# Bt_Drone.net
KiCad netlist of a schematic drawn in EAGLE
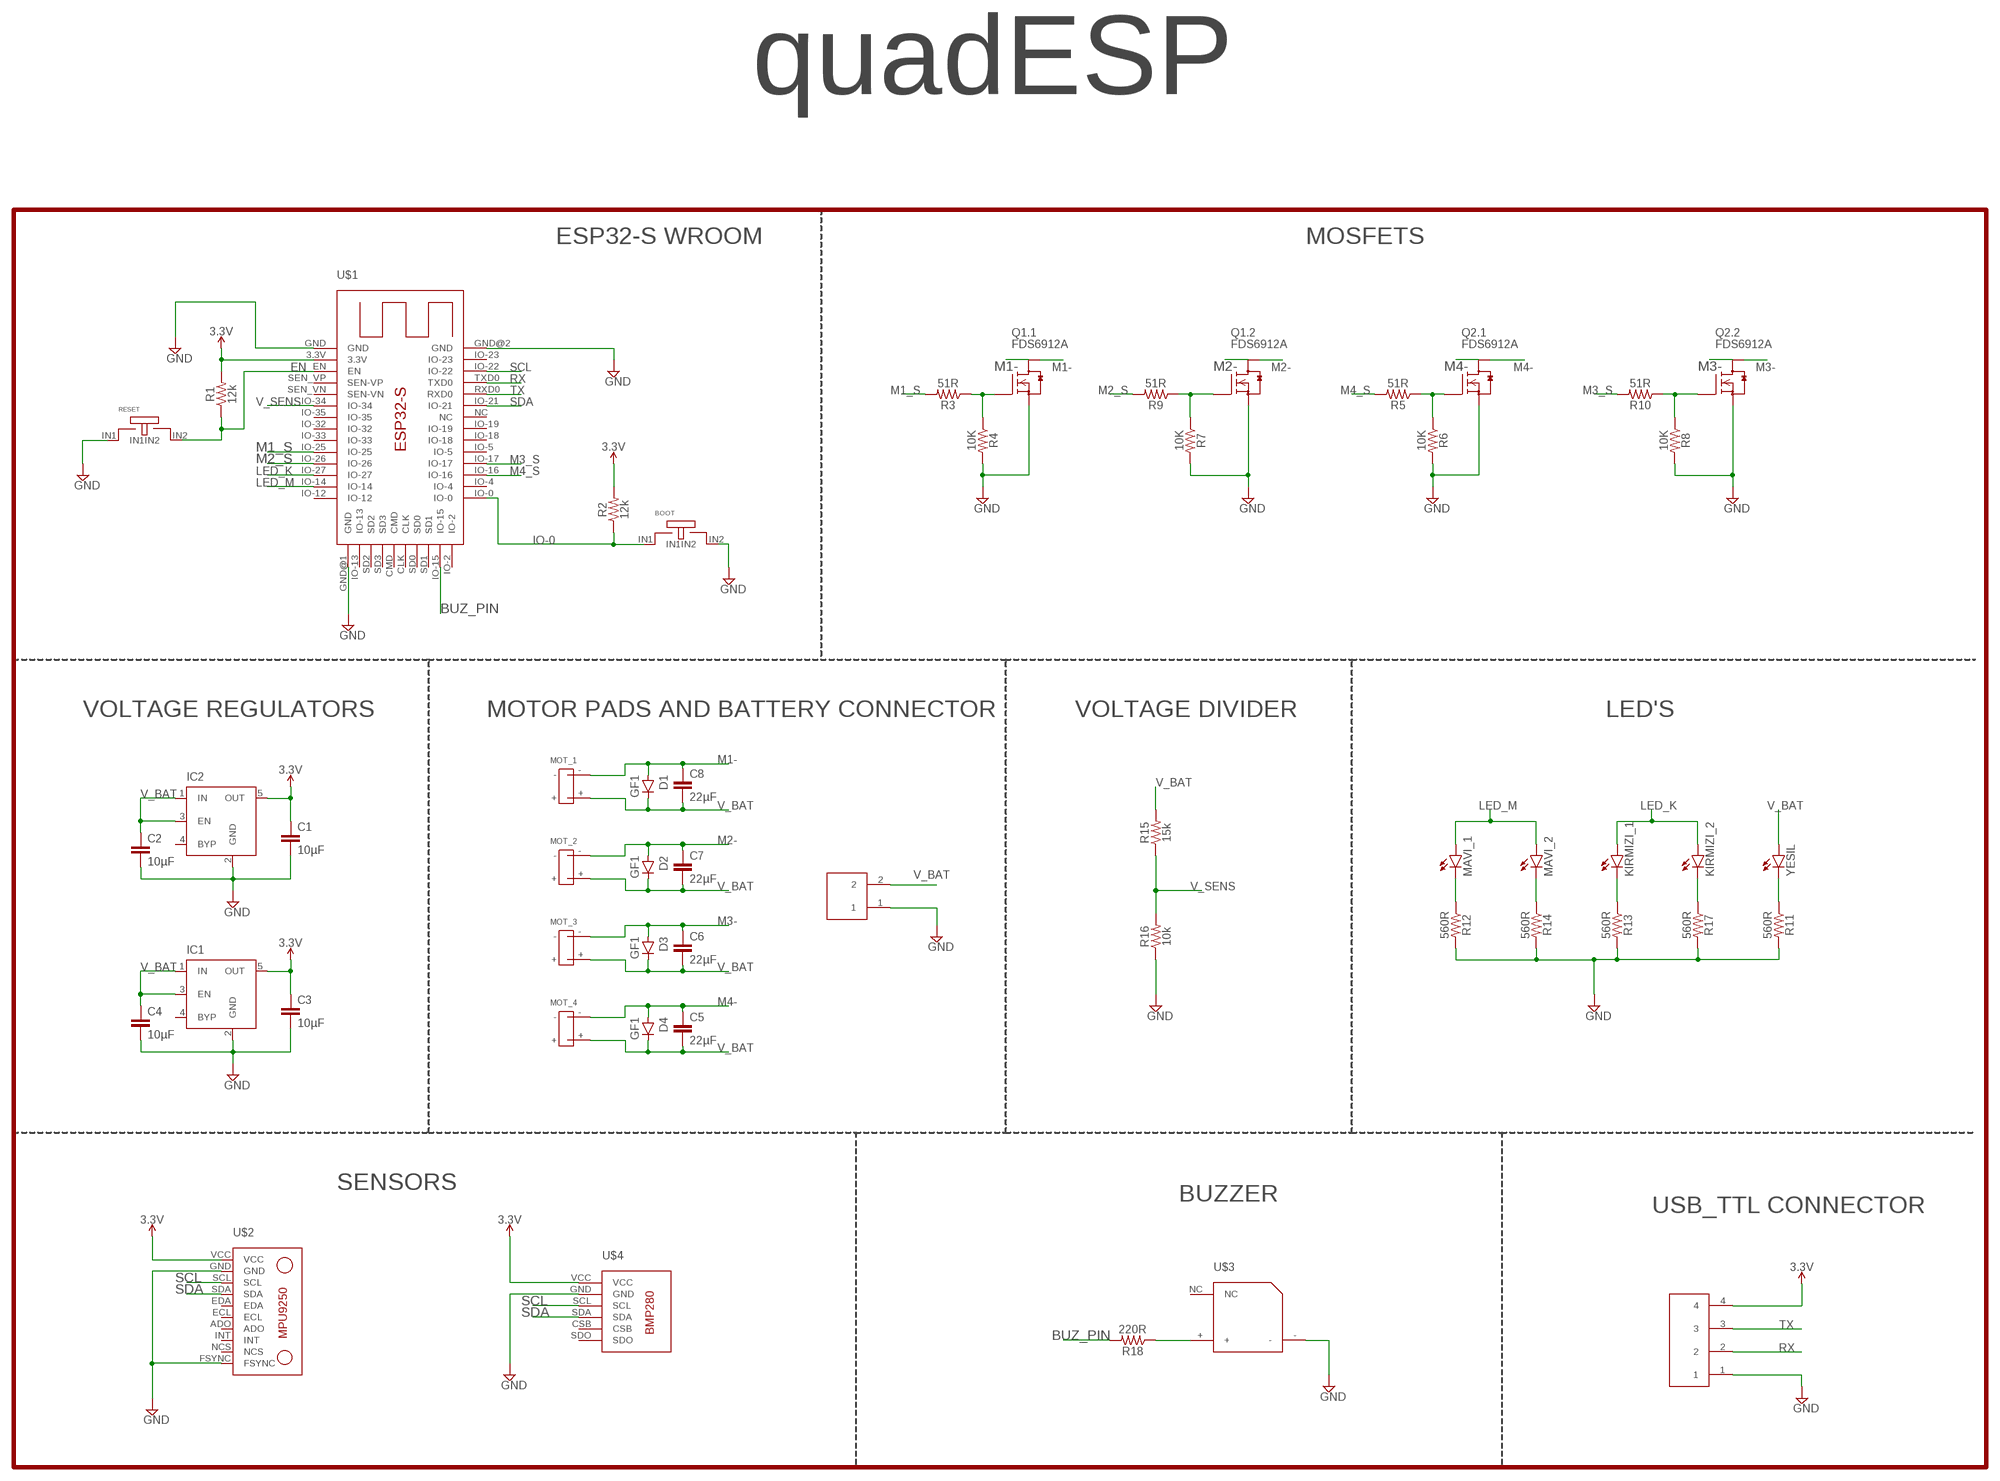
[diagram p0: schematic, sheet 1]

(export (version "E")
  (design (tool "Eeschema 10.0.6"))
  (components
    (comp (ref "BOOT")
      (value "MINI_TIP_SMD_TACT_SWITCH_BUTON")
      (footprint "eagle-import:MINI_TIP_SMD_TACT_SWITCH_BUTON")
      (libsource (lib "eagle-import") (part "MINI_TIP_SMD_TACT_SWITCH_BUTON"))
    )
    (comp (ref "C1")
      (value "10µF")
      (footprint "eagle-import:0805")
      (libsource (lib "eagle-import") (part "0.33UF/330NF-0805-50V-10%"))
    )
    (comp (ref "C2")
      (value "10µF")
      (footprint "eagle-import:0805")
      (libsource (lib "eagle-import") (part "0.33UF/330NF-0805-50V-10%"))
    )
    (comp (ref "C3")
      (value "10µF")
      (footprint "eagle-import:0805")
      (libsource (lib "eagle-import") (part "0.33UF/330NF-0805-50V-10%"))
    )
    (comp (ref "C4")
      (value "10µF")
      (footprint "eagle-import:0805")
      (libsource (lib "eagle-import") (part "0.33UF/330NF-0805-50V-10%"))
    )
    (comp (ref "C5")
      (value "22µF")
      (footprint "eagle-import:0805")
      (libsource (lib "eagle-import") (part "0.33UF/330NF-0805-50V-10%"))
    )
    (comp (ref "C6")
      (value "22µF")
      (footprint "eagle-import:0805")
      (libsource (lib "eagle-import") (part "0.33UF/330NF-0805-50V-10%"))
    )
    (comp (ref "C7")
      (value "22µF")
      (footprint "eagle-import:0805")
      (libsource (lib "eagle-import") (part "0.33UF/330NF-0805-50V-10%"))
    )
    (comp (ref "C8")
      (value "22µF")
      (footprint "eagle-import:0805")
      (libsource (lib "eagle-import") (part "0.33UF/330NF-0805-50V-10%"))
    )
    (comp (ref "D1")
      (value "GF1")
      (footprint "eagle-import:SMA-DO214AC")
      (libsource (lib "eagle-import") (part "GF1"))
    )
    (comp (ref "D2")
      (value "GF1")
      (footprint "eagle-import:SMA-DO214AC")
      (libsource (lib "eagle-import") (part "GF1"))
    )
    (comp (ref "D3")
      (value "GF1")
      (footprint "eagle-import:SMA-DO214AC")
      (libsource (lib "eagle-import") (part "GF1"))
    )
    (comp (ref "D4")
      (value "GF1")
      (footprint "eagle-import:SMA-DO214AC")
      (libsource (lib "eagle-import") (part "GF1"))
    )
    (comp (ref "IC1")
      (value "MIC5219XX")
      (footprint "eagle-import:SOT23-5")
      (libsource (lib "eagle-import") (part "MIC5219XX"))
    )
    (comp (ref "IC2")
      (value "MIC5219XX")
      (footprint "eagle-import:SOT23-5")
      (libsource (lib "eagle-import") (part "MIC5219XX"))
    )
    (comp (ref "KIRMIZI_1")
      (value "LEDCHIP-LED0805")
      (footprint "eagle-import:CHIP-LED0805")
      (libsource (lib "eagle-import") (part "LEDCHIP-LED0805"))
    )
    (comp (ref "KIRMIZI_2")
      (value "LEDCHIP-LED0805")
      (footprint "eagle-import:CHIP-LED0805")
      (libsource (lib "eagle-import") (part "LEDCHIP-LED0805"))
    )
    (comp (ref "MAVI_1")
      (value "LEDCHIP-LED0805")
      (footprint "eagle-import:CHIP-LED0805")
      (libsource (lib "eagle-import") (part "LEDCHIP-LED0805"))
    )
    (comp (ref "MAVI_2")
      (value "LEDCHIP-LED0805")
      (footprint "eagle-import:CHIP-LED0805")
      (libsource (lib "eagle-import") (part "LEDCHIP-LED0805"))
    )
    (comp (ref "MOT_1")
      (value "2X_SOLDER_PAD")
      (footprint "eagle-import:2X_SOLDER_PAD")
      (libsource (lib "eagle-import") (part "2X_SOLDER_PAD"))
    )
    (comp (ref "MOT_2")
      (value "2X_SOLDER_PAD")
      (footprint "eagle-import:2X_SOLDER_PAD")
      (libsource (lib "eagle-import") (part "2X_SOLDER_PAD"))
    )
    (comp (ref "MOT_3")
      (value "2X_SOLDER_PAD")
      (footprint "eagle-import:2X_SOLDER_PAD")
      (libsource (lib "eagle-import") (part "2X_SOLDER_PAD"))
    )
    (comp (ref "MOT_4")
      (value "2X_SOLDER_PAD")
      (footprint "eagle-import:2X_SOLDER_PAD")
      (libsource (lib "eagle-import") (part "2X_SOLDER_PAD"))
    )
    (comp (ref "Q1")
      (value "FDS6912A")
      (footprint "eagle-import:SO-8")
      (libsource (lib "eagle-import") (part "FDS6912A"))
    )
    (comp (ref "Q2")
      (value "FDS6912A")
      (footprint "eagle-import:SO-8")
      (libsource (lib "eagle-import") (part "FDS6912A"))
    )
    (comp (ref "R1")
      (value "12k")
      (footprint "eagle-import:0805")
      (libsource (lib "eagle-import") (part "0.3OHM-0805-1/8W-1%"))
    )
    (comp (ref "R2")
      (value "12k")
      (footprint "eagle-import:0805")
      (libsource (lib "eagle-import") (part "0.3OHM-0805-1/8W-1%"))
    )
    (comp (ref "R3")
      (value "51R")
      (footprint "eagle-import:0805")
      (libsource (lib "eagle-import") (part "0.3OHM-0805-1/8W-1%"))
    )
    (comp (ref "R4")
      (value "10K")
      (footprint "eagle-import:0805")
      (libsource (lib "eagle-import") (part "0.3OHM-0805-1/8W-1%"))
    )
    (comp (ref "R5")
      (value "51R")
      (footprint "eagle-import:0805")
      (libsource (lib "eagle-import") (part "0.3OHM-0805-1/8W-1%"))
    )
    (comp (ref "R6")
      (value "10K")
      (footprint "eagle-import:0805")
      (libsource (lib "eagle-import") (part "0.3OHM-0805-1/8W-1%"))
    )
    (comp (ref "R7")
      (value "10K")
      (footprint "eagle-import:0805")
      (libsource (lib "eagle-import") (part "0.3OHM-0805-1/8W-1%"))
    )
    (comp (ref "R8")
      (value "10K")
      (footprint "eagle-import:0805")
      (libsource (lib "eagle-import") (part "0.3OHM-0805-1/8W-1%"))
    )
    (comp (ref "R9")
      (value "51R")
      (footprint "eagle-import:0805")
      (libsource (lib "eagle-import") (part "0.3OHM-0805-1/8W-1%"))
    )
    (comp (ref "R10")
      (value "51R")
      (footprint "eagle-import:0805")
      (libsource (lib "eagle-import") (part "0.3OHM-0805-1/8W-1%"))
    )
    (comp (ref "R11")
      (value "560R")
      (footprint "eagle-import:0805")
      (libsource (lib "eagle-import") (part "0.3OHM-0805-1/8W-1%"))
    )
    (comp (ref "R12")
      (value "560R")
      (footprint "eagle-import:0805")
      (libsource (lib "eagle-import") (part "0.3OHM-0805-1/8W-1%"))
    )
    (comp (ref "R13")
      (value "560R")
      (footprint "eagle-import:0805")
      (libsource (lib "eagle-import") (part "0.3OHM-0805-1/8W-1%"))
    )
    (comp (ref "R14")
      (value "560R")
      (footprint "eagle-import:0805")
      (libsource (lib "eagle-import") (part "0.3OHM-0805-1/8W-1%"))
    )
    (comp (ref "R15")
      (value "15k")
      (footprint "eagle-import:0805")
      (libsource (lib "eagle-import") (part "0.3OHM-0805-1/8W-1%"))
    )
    (comp (ref "R16")
      (value "10k")
      (footprint "eagle-import:0805")
      (libsource (lib "eagle-import") (part "0.3OHM-0805-1/8W-1%"))
    )
    (comp (ref "R17")
      (value "560R")
      (footprint "eagle-import:0805")
      (libsource (lib "eagle-import") (part "0.3OHM-0805-1/8W-1%"))
    )
    (comp (ref "R18")
      (value "220R")
      (footprint "eagle-import:0805")
      (libsource (lib "eagle-import") (part "0.3OHM-0805-1/8W-1%"))
    )
    (comp (ref "RESET")
      (value "MINI_TIP_SMD_TACT_SWITCH_BUTON")
      (footprint "eagle-import:MINI_TIP_SMD_TACT_SWITCH_BUTON")
      (libsource (lib "eagle-import") (part "MINI_TIP_SMD_TACT_SWITCH_BUTON"))
    )
    (comp (ref "U$1")
      (value "ESP32-S")
      (footprint "eagle-import:ESP32-S")
      (libsource (lib "eagle-import") (part "ESP32-S"))
    )
    (comp (ref "U$2")
      (value "MPU9250")
      (footprint "eagle-import:MPU9250")
      (libsource (lib "eagle-import") (part "MPU9250"))
    )
    (comp (ref "U$3")
      (value "PASIVE_BUZZER_5MM_X_5MM_20MM")
      (footprint "eagle-import:PASIVE_BUZZER_5MM_X_5MM_20MM")
      (libsource (lib "eagle-import") (part "PASIVE_BUZZER_5MM_X_5MM_20MM"))
    )
    (comp (ref "U$4")
      (value "BMP280")
      (footprint "eagle-import:BMP280")
      (libsource (lib "eagle-import") (part "BMP280"))
    )
    (comp (ref "U$5")
      (value "2_PIN_TUNIC")
      (footprint "eagle-import:2_PIN_TUNIC")
      (libsource (lib "eagle-import") (part "2_PIN_TUNIC"))
    )
    (comp (ref "U$6")
      (value "4_PIN_TUNIC")
      (footprint "eagle-import:4_PIN_TUNIC")
      (libsource (lib "eagle-import") (part "4_PIN_TUNIC"))
    )
    (comp (ref "YESIL")
      (value "LEDCHIP-LED0805")
      (footprint "eagle-import:CHIP-LED0805")
      (libsource (lib "eagle-import") (part "LEDCHIP-LED0805"))
    )
  )
  (nets
    (net (code "1") (name "/BUZ_PIN") (class "Default")
      (node (ref "R18") (pin "2") (pinfunction "2_2") (pintype "passive"))
      (node (ref "U$1") (pin "IO-15") (pinfunction "IO-15_IO-15") (pintype "bidirectional"))
    )
    (net (code "2") (name "/EN") (class "Default")
      (node (ref "R1") (pin "1") (pinfunction "1_1") (pintype "passive"))
      (node (ref "RESET") (pin "IN2") (pinfunction "IN2_IN2") (pintype "bidirectional"))
      (node (ref "U$1") (pin "EN") (pinfunction "EN_EN") (pintype "bidirectional"))
    )
    (net (code "3") (name "/IO-0") (class "Default")
      (node (ref "BOOT") (pin "IN1") (pinfunction "IN1_IN1") (pintype "bidirectional"))
      (node (ref "R2") (pin "1") (pinfunction "1_1") (pintype "passive"))
      (node (ref "U$1") (pin "IO-0") (pinfunction "IO-0_IO-0") (pintype "bidirectional"))
    )
    (net (code "4") (name "/LED_K") (class "Default")
      (node (ref "KIRMIZI_1") (pin "A") (pinfunction "A_A") (pintype "passive"))
      (node (ref "KIRMIZI_2") (pin "A") (pinfunction "A_A") (pintype "passive"))
      (node (ref "U$1") (pin "IO-27") (pinfunction "IO-27_IO-27") (pintype "bidirectional"))
    )
    (net (code "5") (name "/LED_M") (class "Default")
      (node (ref "MAVI_1") (pin "A") (pinfunction "A_A") (pintype "passive"))
      (node (ref "MAVI_2") (pin "A") (pinfunction "A_A") (pintype "passive"))
      (node (ref "U$1") (pin "IO-14") (pinfunction "IO-14_IO-14") (pintype "bidirectional"))
    )
    (net (code "6") (name "/M1-") (class "Default")
      (node (ref "C8") (pin "1") (pinfunction "1_1") (pintype "passive"))
      (node (ref "D1") (pin "A") (pinfunction "A_A") (pintype "passive"))
      (node (ref "MOT_1") (pin "-") (pinfunction "-_-") (pintype "bidirectional"))
      (node (ref "Q1") (pin "5") (pinfunction "D_5") (pintype "passive"))
      (node (ref "Q1") (pin "6") (pinfunction "D_6") (pintype "passive"))
    )
    (net (code "7") (name "/M1_S") (class "Default")
      (node (ref "R3") (pin "2") (pinfunction "2_2") (pintype "passive"))
      (node (ref "U$1") (pin "IO-25") (pinfunction "IO-25_IO-25") (pintype "bidirectional"))
    )
    (net (code "8") (name "/M2-") (class "Default")
      (node (ref "C7") (pin "1") (pinfunction "1_1") (pintype "passive"))
      (node (ref "D2") (pin "A") (pinfunction "A_A") (pintype "passive"))
      (node (ref "MOT_2") (pin "-") (pinfunction "-_-") (pintype "bidirectional"))
      (node (ref "Q1") (pin "7") (pinfunction "D_7") (pintype "passive"))
      (node (ref "Q1") (pin "8") (pinfunction "D_8") (pintype "passive"))
    )
    (net (code "9") (name "/M2_S") (class "Default")
      (node (ref "R9") (pin "2") (pinfunction "2_2") (pintype "passive"))
      (node (ref "U$1") (pin "IO-26") (pinfunction "IO-26_IO-26") (pintype "bidirectional"))
    )
    (net (code "10") (name "/M3-") (class "Default")
      (node (ref "C6") (pin "1") (pinfunction "1_1") (pintype "passive"))
      (node (ref "D3") (pin "A") (pinfunction "A_A") (pintype "passive"))
      (node (ref "MOT_3") (pin "-") (pinfunction "-_-") (pintype "bidirectional"))
      (node (ref "Q2") (pin "7") (pinfunction "D_7") (pintype "passive"))
      (node (ref "Q2") (pin "8") (pinfunction "D_8") (pintype "passive"))
    )
    (net (code "11") (name "/M3_S") (class "Default")
      (node (ref "R10") (pin "2") (pinfunction "2_2") (pintype "passive"))
      (node (ref "U$1") (pin "IO-17") (pinfunction "IO-17_IO-17") (pintype "bidirectional"))
    )
    (net (code "12") (name "/M4-") (class "Default")
      (node (ref "C5") (pin "1") (pinfunction "1_1") (pintype "passive"))
      (node (ref "D4") (pin "A") (pinfunction "A_A") (pintype "passive"))
      (node (ref "MOT_4") (pin "-") (pinfunction "-_-") (pintype "bidirectional"))
      (node (ref "Q2") (pin "5") (pinfunction "D_5") (pintype "passive"))
      (node (ref "Q2") (pin "6") (pinfunction "D_6") (pintype "passive"))
    )
    (net (code "13") (name "/M4_S") (class "Default")
      (node (ref "R5") (pin "2") (pinfunction "2_2") (pintype "passive"))
      (node (ref "U$1") (pin "IO-16") (pinfunction "IO-16_IO-16") (pintype "bidirectional"))
    )
    (net (code "14") (name "/RX") (class "Default")
      (node (ref "U$1") (pin "TXD0") (pinfunction "TXD0_TXD0") (pintype "bidirectional"))
      (node (ref "U$6") (pin "2") (pinfunction "2_2") (pintype "bidirectional"))
    )
    (net (code "15") (name "/SCL") (class "Default")
      (node (ref "U$1") (pin "IO-22") (pinfunction "IO-22_IO-22") (pintype "bidirectional"))
      (node (ref "U$2") (pin "SCL") (pinfunction "SCL_SCL") (pintype "bidirectional"))
      (node (ref "U$4") (pin "SCL") (pinfunction "SCL_SCL") (pintype "bidirectional"))
    )
    (net (code "16") (name "/SDA") (class "Default")
      (node (ref "U$1") (pin "IO-21") (pinfunction "IO-21_IO-21") (pintype "bidirectional"))
      (node (ref "U$2") (pin "SDA") (pinfunction "SDA_SDA") (pintype "bidirectional"))
      (node (ref "U$4") (pin "SDA") (pinfunction "SDA_SDA") (pintype "bidirectional"))
    )
    (net (code "17") (name "/TX") (class "Default")
      (node (ref "U$1") (pin "RXD0") (pinfunction "RXD0_RXD0") (pintype "bidirectional"))
      (node (ref "U$6") (pin "3") (pinfunction "3_3") (pintype "bidirectional"))
    )
    (net (code "18") (name "/V_BAT") (class "Default")
      (node (ref "C2") (pin "1") (pinfunction "1_1") (pintype "passive"))
      (node (ref "C4") (pin "1") (pinfunction "1_1") (pintype "passive"))
      (node (ref "C5") (pin "2") (pinfunction "2_2") (pintype "passive"))
      (node (ref "C6") (pin "2") (pinfunction "2_2") (pintype "passive"))
      (node (ref "C7") (pin "2") (pinfunction "2_2") (pintype "passive"))
      (node (ref "C8") (pin "2") (pinfunction "2_2") (pintype "passive"))
      (node (ref "D1") (pin "K") (pinfunction "C_K") (pintype "passive"))
      (node (ref "D2") (pin "K") (pinfunction "C_K") (pintype "passive"))
      (node (ref "D3") (pin "K") (pinfunction "C_K") (pintype "passive"))
      (node (ref "D4") (pin "K") (pinfunction "C_K") (pintype "passive"))
      (node (ref "IC1") (pin "1") (pinfunction "IN_1") (pintype "input"))
      (node (ref "IC1") (pin "3") (pinfunction "EN_3") (pintype "input"))
      (node (ref "IC2") (pin "1") (pinfunction "IN_1") (pintype "input"))
      (node (ref "IC2") (pin "3") (pinfunction "EN_3") (pintype "input"))
      (node (ref "MOT_1") (pin "+") (pinfunction "+_+") (pintype "bidirectional"))
      (node (ref "MOT_2") (pin "+") (pinfunction "+_+") (pintype "bidirectional"))
      (node (ref "MOT_3") (pin "+") (pinfunction "+_+") (pintype "bidirectional"))
      (node (ref "MOT_4") (pin "+") (pinfunction "+_+") (pintype "bidirectional"))
      (node (ref "R15") (pin "2") (pinfunction "2_2") (pintype "passive"))
      (node (ref "U$5") (pin "2") (pinfunction "2_2") (pintype "bidirectional"))
      (node (ref "YESIL") (pin "A") (pinfunction "A_A") (pintype "passive"))
    )
    (net (code "19") (name "/V_SENS") (class "Default")
      (node (ref "R15") (pin "1") (pinfunction "1_1") (pintype "passive"))
      (node (ref "R16") (pin "2") (pinfunction "2_2") (pintype "passive"))
      (node (ref "U$1") (pin "IO-34") (pinfunction "IO-34_IO-34") (pintype "bidirectional"))
    )
    (net (code "20") (name "3.3V") (class "Default")
      (node (ref "C1") (pin "1") (pinfunction "1_1") (pintype "passive"))
      (node (ref "C3") (pin "1") (pinfunction "1_1") (pintype "passive"))
      (node (ref "IC1") (pin "5") (pinfunction "OUT_5") (pintype "output"))
      (node (ref "IC2") (pin "5") (pinfunction "OUT_5") (pintype "output"))
      (node (ref "R1") (pin "2") (pinfunction "2_2") (pintype "passive"))
      (node (ref "R2") (pin "2") (pinfunction "2_2") (pintype "passive"))
      (node (ref "U$1") (pin "3.3V") (pinfunction "3.3V_3.3V") (pintype "bidirectional"))
      (node (ref "U$2") (pin "VCC") (pinfunction "VCC_VCC") (pintype "bidirectional"))
      (node (ref "U$4") (pin "VCC") (pinfunction "VCC_VCC") (pintype "bidirectional"))
      (node (ref "U$6") (pin "4") (pinfunction "4_4") (pintype "bidirectional"))
    )
    (net (code "21") (name "GND") (class "Default")
      (node (ref "BOOT") (pin "IN2") (pinfunction "IN2_IN2") (pintype "bidirectional"))
      (node (ref "C1") (pin "2") (pinfunction "2_2") (pintype "passive"))
      (node (ref "C2") (pin "2") (pinfunction "2_2") (pintype "passive"))
      (node (ref "C3") (pin "2") (pinfunction "2_2") (pintype "passive"))
      (node (ref "C4") (pin "2") (pinfunction "2_2") (pintype "passive"))
      (node (ref "IC1") (pin "2") (pinfunction "GND_2") (pintype "power_in"))
      (node (ref "IC2") (pin "2") (pinfunction "GND_2") (pintype "power_in"))
      (node (ref "Q1") (pin "1") (pinfunction "S_1") (pintype "passive"))
      (node (ref "Q1") (pin "3") (pinfunction "S_3") (pintype "passive"))
      (node (ref "Q2") (pin "1") (pinfunction "S_1") (pintype "passive"))
      (node (ref "Q2") (pin "3") (pinfunction "S_3") (pintype "passive"))
      (node (ref "R11") (pin "2") (pinfunction "2_2") (pintype "passive"))
      (node (ref "R12") (pin "2") (pinfunction "2_2") (pintype "passive"))
      (node (ref "R13") (pin "2") (pinfunction "2_2") (pintype "passive"))
      (node (ref "R14") (pin "2") (pinfunction "2_2") (pintype "passive"))
      (node (ref "R16") (pin "1") (pinfunction "1_1") (pintype "passive"))
      (node (ref "R17") (pin "2") (pinfunction "2_2") (pintype "passive"))
      (node (ref "R4") (pin "2") (pinfunction "2_2") (pintype "passive"))
      (node (ref "R6") (pin "2") (pinfunction "2_2") (pintype "passive"))
      (node (ref "R7") (pin "2") (pinfunction "2_2") (pintype "passive"))
      (node (ref "R8") (pin "2") (pinfunction "2_2") (pintype "passive"))
      (node (ref "RESET") (pin "IN1") (pinfunction "IN1_IN1") (pintype "bidirectional"))
      (node (ref "U$1") (pin "GND") (pinfunction "GND_GND") (pintype "bidirectional"))
      (node (ref "U$1") (pin "GND@1") (pinfunction "GND_GND@1") (pintype "bidirectional"))
      (node (ref "U$1") (pin "GND@2") (pinfunction "GND_GND@2") (pintype "bidirectional"))
      (node (ref "U$2") (pin "FSYNC") (pinfunction "FSYNC_FSYNC") (pintype "bidirectional"))
      (node (ref "U$2") (pin "GND") (pinfunction "GND_GND") (pintype "bidirectional"))
      (node (ref "U$3") (pin "-") (pinfunction "-_-") (pintype "bidirectional"))
      (node (ref "U$4") (pin "GND") (pinfunction "GND_GND") (pintype "bidirectional"))
      (node (ref "U$5") (pin "1") (pinfunction "1_1") (pintype "bidirectional"))
      (node (ref "U$6") (pin "1") (pinfunction "1_1") (pintype "bidirectional"))
    )
    (net (code "22") (name "Net-(KIRMIZI_1-PadC)") (class "Default")
      (node (ref "KIRMIZI_1") (pin "C") (pinfunction "C_C") (pintype "passive"))
      (node (ref "R13") (pin "1") (pinfunction "1_1") (pintype "passive"))
    )
    (net (code "23") (name "Net-(KIRMIZI_2-PadC)") (class "Default")
      (node (ref "KIRMIZI_2") (pin "C") (pinfunction "C_C") (pintype "passive"))
      (node (ref "R17") (pin "1") (pinfunction "1_1") (pintype "passive"))
    )
    (net (code "24") (name "Net-(MAVI_1-PadC)") (class "Default")
      (node (ref "MAVI_1") (pin "C") (pinfunction "C_C") (pintype "passive"))
      (node (ref "R12") (pin "1") (pinfunction "1_1") (pintype "passive"))
    )
    (net (code "25") (name "Net-(MAVI_2-PadC)") (class "Default")
      (node (ref "MAVI_2") (pin "C") (pinfunction "C_C") (pintype "passive"))
      (node (ref "R14") (pin "1") (pinfunction "1_1") (pintype "passive"))
    )
    (net (code "26") (name "Net-(Q1A-G)") (class "Default")
      (node (ref "Q1") (pin "4") (pinfunction "G_4") (pintype "passive"))
      (node (ref "R3") (pin "1") (pinfunction "1_1") (pintype "passive"))
      (node (ref "R4") (pin "1") (pinfunction "1_1") (pintype "passive"))
    )
    (net (code "27") (name "Net-(Q1B-G)") (class "Default")
      (node (ref "Q1") (pin "2") (pinfunction "G_2") (pintype "passive"))
      (node (ref "R7") (pin "1") (pinfunction "1_1") (pintype "passive"))
      (node (ref "R9") (pin "1") (pinfunction "1_1") (pintype "passive"))
    )
    (net (code "28") (name "Net-(Q2A-G)") (class "Default")
      (node (ref "Q2") (pin "4") (pinfunction "G_4") (pintype "passive"))
      (node (ref "R5") (pin "1") (pinfunction "1_1") (pintype "passive"))
      (node (ref "R6") (pin "1") (pinfunction "1_1") (pintype "passive"))
    )
    (net (code "29") (name "Net-(Q2B-G)") (class "Default")
      (node (ref "Q2") (pin "2") (pinfunction "G_2") (pintype "passive"))
      (node (ref "R10") (pin "1") (pinfunction "1_1") (pintype "passive"))
      (node (ref "R8") (pin "1") (pinfunction "1_1") (pintype "passive"))
    )
    (net (code "30") (name "Net-(R11-Pad1)") (class "Default")
      (node (ref "R11") (pin "1") (pinfunction "1_1") (pintype "passive"))
      (node (ref "YESIL") (pin "C") (pinfunction "C_C") (pintype "passive"))
    )
    (net (code "31") (name "Net-(R18-Pad1)") (class "Default")
      (node (ref "R18") (pin "1") (pinfunction "1_1") (pintype "passive"))
      (node (ref "U$3") (pin "+") (pinfunction "+_+") (pintype "bidirectional"))
    )
    (net (code "32") (name "unconnected-(IC1-BYP-Pad4)") (class "Default")
      (node (ref "IC1") (pin "4") (pinfunction "BYP_4") (pintype "passive"))
    )
    (net (code "33") (name "unconnected-(IC2-BYP-Pad4)") (class "Default")
      (node (ref "IC2") (pin "4") (pinfunction "BYP_4") (pintype "passive"))
    )
    (net (code "34") (name "unconnected-(U$1-PadCLK)") (class "Default")
      (node (ref "U$1") (pin "CLK") (pinfunction "CLK_CLK") (pintype "bidirectional"))
    )
    (net (code "35") (name "unconnected-(U$1-PadCMD)") (class "Default")
      (node (ref "U$1") (pin "CMD") (pinfunction "CMD_CMD") (pintype "bidirectional"))
    )
    (net (code "36") (name "unconnected-(U$1-PadIO-2)") (class "Default")
      (node (ref "U$1") (pin "IO-2") (pinfunction "IO-2_IO-2") (pintype "bidirectional"))
    )
    (net (code "37") (name "unconnected-(U$1-PadIO-4)") (class "Default")
      (node (ref "U$1") (pin "IO-4") (pinfunction "IO-4_IO-4") (pintype "bidirectional"))
    )
    (net (code "38") (name "unconnected-(U$1-PadIO-5)") (class "Default")
      (node (ref "U$1") (pin "IO-5") (pinfunction "IO-5_IO-5") (pintype "bidirectional"))
    )
    (net (code "39") (name "unconnected-(U$1-PadIO-12)") (class "Default")
      (node (ref "U$1") (pin "IO-12") (pinfunction "IO-12_IO-12") (pintype "bidirectional"))
    )
    (net (code "40") (name "unconnected-(U$1-PadIO-13)") (class "Default")
      (node (ref "U$1") (pin "IO-13") (pinfunction "IO-13_IO-13") (pintype "bidirectional"))
    )
    (net (code "41") (name "unconnected-(U$1-PadIO-18)") (class "Default")
      (node (ref "U$1") (pin "IO-18") (pinfunction "IO-18_IO-18") (pintype "bidirectional"))
    )
    (net (code "42") (name "unconnected-(U$1-PadIO-19)") (class "Default")
      (node (ref "U$1") (pin "IO-19") (pinfunction "IO-19_IO-19") (pintype "bidirectional"))
    )
    (net (code "43") (name "unconnected-(U$1-PadIO-23)") (class "Default")
      (node (ref "U$1") (pin "IO-23") (pinfunction "IO-23_IO-23") (pintype "bidirectional"))
    )
    (net (code "44") (name "unconnected-(U$1-PadIO-32)") (class "Default")
      (node (ref "U$1") (pin "IO-32") (pinfunction "IO-32_IO-32") (pintype "bidirectional"))
    )
    (net (code "45") (name "unconnected-(U$1-PadIO-33)") (class "Default")
      (node (ref "U$1") (pin "IO-33") (pinfunction "IO-33_IO-33") (pintype "bidirectional"))
    )
    (net (code "46") (name "unconnected-(U$1-PadIO-35)") (class "Default")
      (node (ref "U$1") (pin "IO-35") (pinfunction "IO-35_IO-35") (pintype "bidirectional"))
    )
    (net (code "47") (name "unconnected-(U$1-PadNC)") (class "Default")
      (node (ref "U$1") (pin "NC") (pinfunction "NC_NC") (pintype "bidirectional"))
    )
    (net (code "48") (name "unconnected-(U$1-PadSD0)") (class "Default")
      (node (ref "U$1") (pin "SD0") (pinfunction "SD0_SD0") (pintype "bidirectional"))
    )
    (net (code "49") (name "unconnected-(U$1-PadSD1)") (class "Default")
      (node (ref "U$1") (pin "SD1") (pinfunction "SD1_SD1") (pintype "bidirectional"))
    )
    (net (code "50") (name "unconnected-(U$1-PadSD2)") (class "Default")
      (node (ref "U$1") (pin "SD2") (pinfunction "SD2_SD2") (pintype "bidirectional"))
    )
    (net (code "51") (name "unconnected-(U$1-PadSD3)") (class "Default")
      (node (ref "U$1") (pin "SD3") (pinfunction "SD3_SD3") (pintype "bidirectional"))
    )
    (net (code "52") (name "unconnected-(U$1-SEN-VN-PadSEN_VN)") (class "Default")
      (node (ref "U$1") (pin "SEN_VN") (pinfunction "SEN-VN_SEN_VN") (pintype "bidirectional"))
    )
    (net (code "53") (name "unconnected-(U$1-SEN-VP-PadSEN_VP)") (class "Default")
      (node (ref "U$1") (pin "SEN_VP") (pinfunction "SEN-VP_SEN_VP") (pintype "bidirectional"))
    )
    (net (code "54") (name "unconnected-(U$2-PadADO)") (class "Default")
      (node (ref "U$2") (pin "ADO") (pinfunction "ADO_ADO") (pintype "bidirectional"))
    )
    (net (code "55") (name "unconnected-(U$2-PadECL)") (class "Default")
      (node (ref "U$2") (pin "ECL") (pinfunction "ECL_ECL") (pintype "bidirectional"))
    )
    (net (code "56") (name "unconnected-(U$2-PadEDA)") (class "Default")
      (node (ref "U$2") (pin "EDA") (pinfunction "EDA_EDA") (pintype "bidirectional"))
    )
    (net (code "57") (name "unconnected-(U$2-PadINT)") (class "Default")
      (node (ref "U$2") (pin "INT") (pinfunction "INT_INT") (pintype "bidirectional"))
    )
    (net (code "58") (name "unconnected-(U$2-PadNCS)") (class "Default")
      (node (ref "U$2") (pin "NCS") (pinfunction "NCS_NCS") (pintype "bidirectional"))
    )
    (net (code "59") (name "unconnected-(U$3-PadNC)") (class "Default")
      (node (ref "U$3") (pin "NC") (pinfunction "NC_NC") (pintype "bidirectional"))
    )
    (net (code "60") (name "unconnected-(U$4-PadCSB)") (class "Default")
      (node (ref "U$4") (pin "CSB") (pinfunction "CSB_CSB") (pintype "bidirectional"))
    )
    (net (code "61") (name "unconnected-(U$4-PadSDO)") (class "Default")
      (node (ref "U$4") (pin "SDO") (pinfunction "SDO_SDO") (pintype "bidirectional"))
    )
  )
)
